# Power.net
KiCad netlist of a schematic drawn in Altium Designer
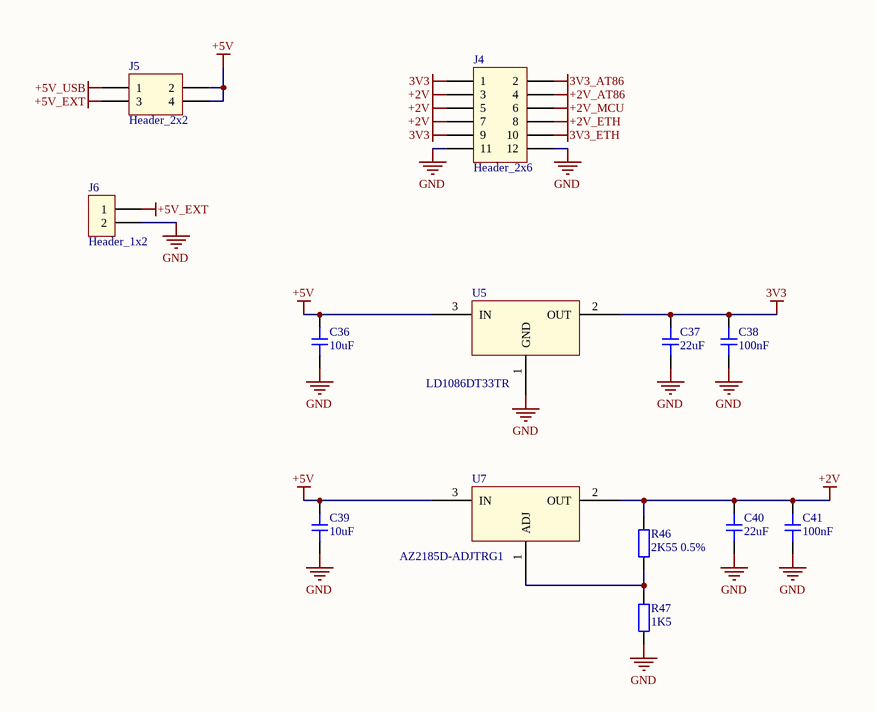
[diagram p0: Power.SchDoc]

(export (version "E")
  (design (tool "Eeschema 10.0.6"))
  (components
    (comp (ref "C36")
      (value "10uF")
      (footprint "Capacitor-1210")
      (fields (field (name "Comment") "C-10uF-1210"))
      (libsource (lib "Components") (part "C-10uF-1210"))
    )
    (comp (ref "C37")
      (value "22uF")
      (footprint "Capacitor-1210")
      (fields (field (name "Comment") "C-22uF-1210"))
      (libsource (lib "Components") (part "C-22uF-1210"))
    )
    (comp (ref "C38")
      (value "100nF")
      (footprint "Capacitor-0603")
      (fields (field (name "Comment") "C-100nF-0603"))
      (libsource (lib "Components") (part "C-100nF-0603"))
    )
    (comp (ref "C39")
      (value "10uF")
      (footprint "Capacitor-1210")
      (fields (field (name "Comment") "C-10uF-1210"))
      (libsource (lib "Components") (part "C-10uF-1210"))
    )
    (comp (ref "C40")
      (value "22uF")
      (footprint "Capacitor-1210")
      (fields (field (name "Comment") "C-22uF-1210"))
      (libsource (lib "Components") (part "C-22uF-1210"))
    )
    (comp (ref "C41")
      (value "100nF")
      (footprint "Capacitor-0603")
      (fields (field (name "Comment") "C-100nF-0603"))
      (libsource (lib "Components") (part "C-100nF-0603"))
    )
    (comp (ref "J4")
      (value "Header_2x6")
      (footprint "Header_2x6")
      (libsource (lib "Components") (part "Header_2x6"))
    )
    (comp (ref "J5")
      (value "Header_2x2")
      (footprint "Header_2x2")
      (libsource (lib "Components") (part "Header_2x2"))
    )
    (comp (ref "J6")
      (value "Header_1x2")
      (footprint "Header_1x2")
      (libsource (lib "Components") (part "Header_1x2"))
    )
    (comp (ref "R46")
      (value "2K55 0.5%")
      (footprint "Resistor-0603")
      (fields (field (name "Comment") "R-2K55-0603"))
      (libsource (lib "Components") (part "R-2K55-0603"))
    )
    (comp (ref "R47")
      (value "1K5")
      (footprint "Resistor-0603")
      (fields (field (name "Comment") "R-1K5-0603"))
      (libsource (lib "Components") (part "R-1K5-0603"))
    )
    (comp (ref "U5")
      (value "LD1086DT33TR")
      (footprint "LD1086DT33TR")
      (libsource (lib "Components") (part "LD1086DT33TR"))
    )
    (comp (ref "U7")
      (value "AZ2185D-ADJTRG1")
      (footprint "AZ2185D-ADJTRG1")
      (libsource (lib "Components") (part "AZ2185D-ADJTRG1"))
    )
  )
  (nets
    (net (code "1") (name "+2V") (class "Default")
      (node (ref "C40") (pin "2") (pinfunction "2_2") (pintype "passive"))
      (node (ref "C41") (pin "2") (pinfunction "2_2") (pintype "passive"))
      (node (ref "J4") (pin "3") (pinfunction "3_3") (pintype "passive"))
      (node (ref "J4") (pin "5") (pinfunction "5_5") (pintype "passive"))
      (node (ref "J4") (pin "7") (pinfunction "7_7") (pintype "passive"))
      (node (ref "R46") (pin "2") (pinfunction "2_2") (pintype "passive"))
      (node (ref "U7") (pin "2") (pinfunction "OUT_2") (pintype "passive"))
    )
    (net (code "2") (name "+2V_AT86") (class "Default")
      (node (ref "J4") (pin "4") (pinfunction "4_4") (pintype "passive"))
    )
    (net (code "3") (name "+2V_ETH") (class "Default")
      (node (ref "J4") (pin "8") (pinfunction "8_8") (pintype "passive"))
    )
    (net (code "4") (name "+2V_MCU") (class "Default")
      (node (ref "J4") (pin "6") (pinfunction "6_6") (pintype "passive"))
    )
    (net (code "5") (name "+5V") (class "Default")
      (node (ref "C36") (pin "2") (pinfunction "2_2") (pintype "passive"))
      (node (ref "C39") (pin "2") (pinfunction "2_2") (pintype "passive"))
      (node (ref "J5") (pin "2") (pinfunction "2_2") (pintype "passive"))
      (node (ref "J5") (pin "4") (pinfunction "4_4") (pintype "passive"))
      (node (ref "U5") (pin "3") (pinfunction "IN_3") (pintype "passive"))
      (node (ref "U7") (pin "3") (pinfunction "IN_3") (pintype "passive"))
    )
    (net (code "6") (name "+5V_EXT") (class "Default")
      (node (ref "J5") (pin "3") (pinfunction "3_3") (pintype "passive"))
      (node (ref "J6") (pin "1") (pinfunction "1_1") (pintype "passive"))
    )
    (net (code "7") (name "+5V_USB") (class "Default")
      (node (ref "J5") (pin "1") (pinfunction "1_1") (pintype "passive"))
    )
    (net (code "8") (name "3V3") (class "Default")
      (node (ref "C37") (pin "2") (pinfunction "2_2") (pintype "passive"))
      (node (ref "C38") (pin "2") (pinfunction "2_2") (pintype "passive"))
      (node (ref "J4") (pin "1") (pinfunction "1_1") (pintype "passive"))
      (node (ref "J4") (pin "9") (pinfunction "9_9") (pintype "passive"))
      (node (ref "U5") (pin "2") (pinfunction "OUT_2") (pintype "passive"))
    )
    (net (code "9") (name "3V3_AT86") (class "Default")
      (node (ref "J4") (pin "2") (pinfunction "2_2") (pintype "passive"))
    )
    (net (code "10") (name "3V3_ETH") (class "Default")
      (node (ref "J4") (pin "10") (pinfunction "10_10") (pintype "passive"))
    )
    (net (code "11") (name "GND") (class "Default")
      (node (ref "C36") (pin "1") (pinfunction "1_1") (pintype "passive"))
      (node (ref "C37") (pin "1") (pinfunction "1_1") (pintype "passive"))
      (node (ref "C38") (pin "1") (pinfunction "1_1") (pintype "passive"))
      (node (ref "C39") (pin "1") (pinfunction "1_1") (pintype "passive"))
      (node (ref "C40") (pin "1") (pinfunction "1_1") (pintype "passive"))
      (node (ref "C41") (pin "1") (pinfunction "1_1") (pintype "passive"))
      (node (ref "J4") (pin "11") (pinfunction "11_11") (pintype "passive"))
      (node (ref "J4") (pin "12") (pinfunction "12_12") (pintype "passive"))
      (node (ref "J6") (pin "2") (pinfunction "2_2") (pintype "passive"))
      (node (ref "R47") (pin "1") (pinfunction "1_1") (pintype "passive"))
      (node (ref "U5") (pin "1") (pinfunction "GND_1") (pintype "passive"))
    )
    (net (code "12") (name "Net-(U7-ADJ)") (class "Default")
      (node (ref "R46") (pin "1") (pinfunction "1_1") (pintype "passive"))
      (node (ref "R47") (pin "2") (pinfunction "2_2") (pintype "passive"))
      (node (ref "U7") (pin "1") (pinfunction "ADJ_1") (pintype "passive"))
    )
  )
)
